# MCPAmplifier.net
KiCad netlist of a schematic drawn in EAGLE
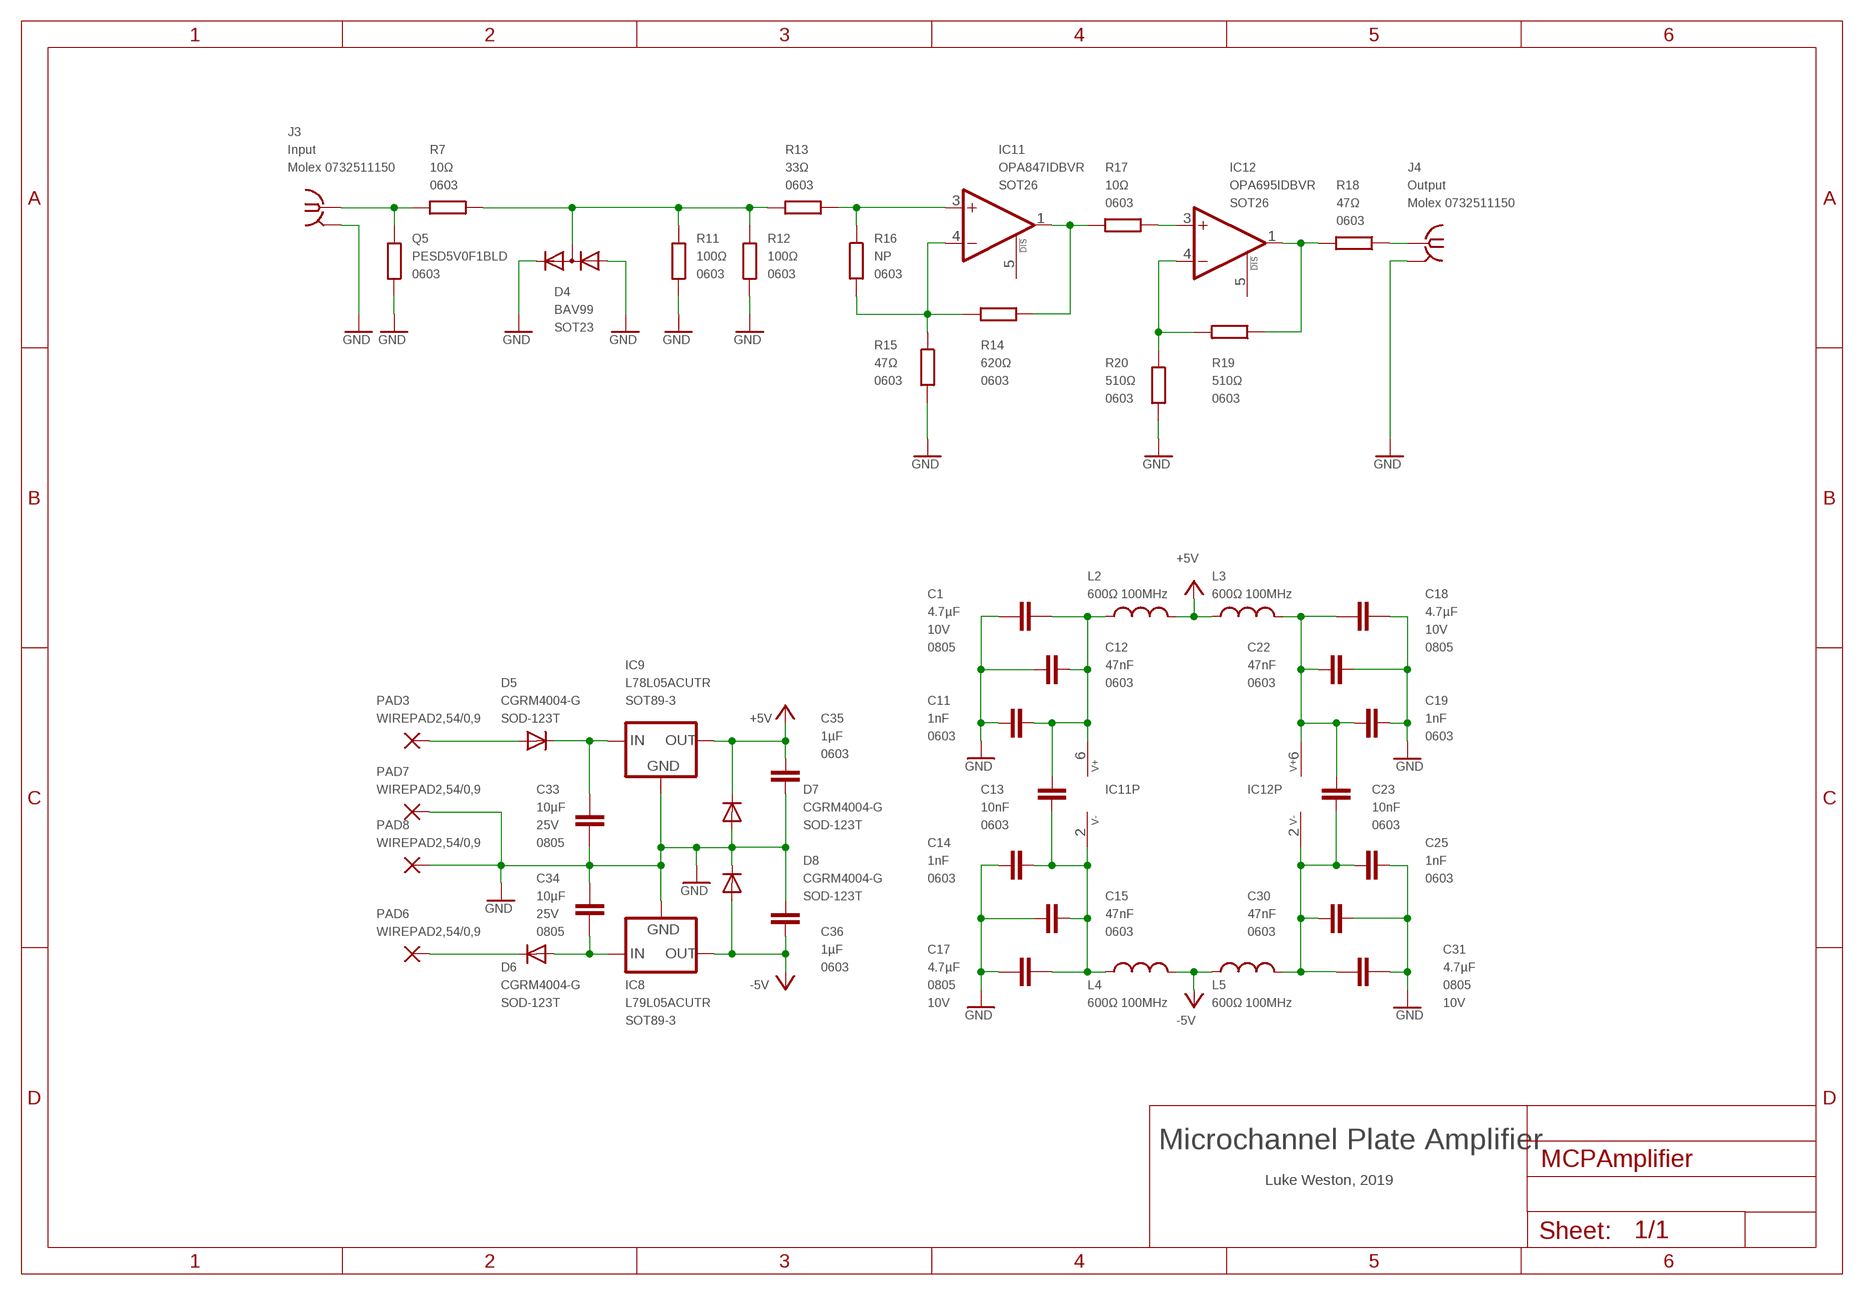
[diagram p0: schematic, sheet 1]

(export (version "E")
  (design (tool "Eeschema 10.0.6"))
  (components
    (comp (ref "C1")
      (value "4.7µF")
      (footprint "eagle-import:0805")
      (fields (field (name "PACKAGE") "0805") (field (name "VOLTAGE") "10V"))
      (libsource (lib "eagle-import") (part "CAP0805"))
    )
    (comp (ref "C11")
      (value "1nF")
      (footprint "eagle-import:0603")
      (fields (field (name "PACKAGE") "0603"))
      (libsource (lib "eagle-import") (part "C0603"))
    )
    (comp (ref "C12")
      (value "47nF")
      (footprint "eagle-import:0603")
      (fields (field (name "PACKAGE") "0603"))
      (libsource (lib "eagle-import") (part "C0603"))
    )
    (comp (ref "C13")
      (value "10nF")
      (footprint "eagle-import:0603")
      (fields (field (name "PACKAGE") "0603"))
      (libsource (lib "eagle-import") (part "C0603"))
    )
    (comp (ref "C14")
      (value "1nF")
      (footprint "eagle-import:0603")
      (fields (field (name "PACKAGE") "0603"))
      (libsource (lib "eagle-import") (part "C0603"))
    )
    (comp (ref "C15")
      (value "47nF")
      (footprint "eagle-import:0603")
      (fields (field (name "PACKAGE") "0603"))
      (libsource (lib "eagle-import") (part "C0603"))
    )
    (comp (ref "C17")
      (value "4.7µF")
      (footprint "eagle-import:0805")
      (fields (field (name "PACKAGE") "0805") (field (name "VOLTAGE") "10V"))
      (libsource (lib "eagle-import") (part "CAP0805"))
    )
    (comp (ref "C18")
      (value "4.7µF")
      (footprint "eagle-import:0805")
      (fields (field (name "PACKAGE") "0805") (field (name "VOLTAGE") "10V"))
      (libsource (lib "eagle-import") (part "CAP0805"))
    )
    (comp (ref "C19")
      (value "1nF")
      (footprint "eagle-import:0603")
      (fields (field (name "PACKAGE") "0603"))
      (libsource (lib "eagle-import") (part "C0603"))
    )
    (comp (ref "C22")
      (value "47nF")
      (footprint "eagle-import:0603")
      (fields (field (name "PACKAGE") "0603"))
      (libsource (lib "eagle-import") (part "C0603"))
    )
    (comp (ref "C23")
      (value "10nF")
      (footprint "eagle-import:0603")
      (fields (field (name "PACKAGE") "0603"))
      (libsource (lib "eagle-import") (part "C0603"))
    )
    (comp (ref "C25")
      (value "1nF")
      (footprint "eagle-import:0603")
      (fields (field (name "PACKAGE") "0603"))
      (libsource (lib "eagle-import") (part "C0603"))
    )
    (comp (ref "C30")
      (value "47nF")
      (footprint "eagle-import:0603")
      (fields (field (name "PACKAGE") "0603"))
      (libsource (lib "eagle-import") (part "C0603"))
    )
    (comp (ref "C31")
      (value "4.7µF")
      (footprint "eagle-import:0805")
      (fields (field (name "PACKAGE") "0805") (field (name "VOLTAGE") "10V"))
      (libsource (lib "eagle-import") (part "CAP0805"))
    )
    (comp (ref "C33")
      (value "10µF")
      (footprint "eagle-import:0805")
      (fields (field (name "PACKAGE") "0805") (field (name "VOLTAGE") "25V"))
      (libsource (lib "eagle-import") (part "CAP0805"))
    )
    (comp (ref "C34")
      (value "10µF")
      (footprint "eagle-import:0805")
      (fields (field (name "PACKAGE") "0805") (field (name "VOLTAGE") "25V"))
      (libsource (lib "eagle-import") (part "CAP0805"))
    )
    (comp (ref "C35")
      (value "1µF")
      (footprint "eagle-import:0603")
      (fields (field (name "PACKAGE") "0603"))
      (libsource (lib "eagle-import") (part "C0603"))
    )
    (comp (ref "C36")
      (value "1µF")
      (footprint "eagle-import:0603")
      (fields (field (name "PACKAGE") "0603"))
      (libsource (lib "eagle-import") (part "C0603"))
    )
    (comp (ref "D4")
      (value "BAV99")
      (footprint "eagle-import:SOT23")
      (fields (field (name "PACKAGE") "SOT23"))
      (libsource (lib "eagle-import") (part "BAV199"))
    )
    (comp (ref "D5")
      (value "CGRM4004-G")
      (footprint "eagle-import:SOD-123_MINI-SMA")
      (fields (field (name "PACKAGE") "SOD-123T"))
      (libsource (lib "eagle-import") (part "CGRM400-G4"))
    )
    (comp (ref "D6")
      (value "CGRM4004-G")
      (footprint "eagle-import:SOD-123_MINI-SMA")
      (fields (field (name "PACKAGE") "SOD-123T"))
      (libsource (lib "eagle-import") (part "CGRM400-G4"))
    )
    (comp (ref "D7")
      (value "CGRM4004-G")
      (footprint "eagle-import:SOD-123_MINI-SMA")
      (fields (field (name "PACKAGE") "SOD-123T"))
      (libsource (lib "eagle-import") (part "CGRM400-G4"))
    )
    (comp (ref "D8")
      (value "CGRM4004-G")
      (footprint "eagle-import:SOD-123_MINI-SMA")
      (fields (field (name "PACKAGE") "SOD-123T"))
      (libsource (lib "eagle-import") (part "CGRM400-G4"))
    )
    (comp (ref "IC8")
      (value "L79L05ACUTR")
      (footprint "eagle-import:SOT89")
      (fields (field (name "PACKAGE") "SOT89-3"))
      (libsource (lib "eagle-import") (part "79LXX-SOT89"))
    )
    (comp (ref "IC9")
      (value "L78L05ACUTR")
      (footprint "eagle-import:SOT89")
      (fields (field (name "PACKAGE") "SOT89-3"))
      (libsource (lib "eagle-import") (part "78LXX-SOT89"))
    )
    (comp (ref "IC11")
      (value "OPA847IDBVR")
      (footprint "eagle-import:SOT23-6")
      (fields (field (name "PACKAGE") "SOT26"))
      (libsource (lib "eagle-import") (part "OPA847DBV"))
    )
    (comp (ref "IC12")
      (value "OPA695IDBVR")
      (footprint "eagle-import:SOT23-6")
      (fields (field (name "PACKAGE") "SOT26"))
      (libsource (lib "eagle-import") (part "OPA847DBV"))
    )
    (comp (ref "J3")
      (value "Input")
      (footprint "eagle-import:J502-ND-142-0701-881_886")
      (fields
        (field (name "MF") "JOHNSON COMPONENTS")
        (field (name "MPN") "142-0701-881")
        (field (name "SKU") "Molex 0732511150")
      )
      (libsource (lib "eagle-import") (part "SMA-142-0701-881/886"))
    )
    (comp (ref "J4")
      (value "Output")
      (footprint "eagle-import:J502-ND-142-0701-881_886")
      (fields
        (field (name "MF") "JOHNSON COMPONENTS")
        (field (name "MPN") "142-0701-881")
        (field (name "SKU") "Molex 0732511150")
      )
      (libsource (lib "eagle-import") (part "SMA-142-0701-881/886"))
    )
    (comp (ref "L2")
      (value "600Ω 100MHz")
      (footprint "eagle-import:0603")
      (libsource (lib "eagle-import") (part "0402INDUCTOR"))
    )
    (comp (ref "L3")
      (value "600Ω 100MHz")
      (footprint "eagle-import:0603")
      (libsource (lib "eagle-import") (part "0402INDUCTOR"))
    )
    (comp (ref "L4")
      (value "600Ω 100MHz")
      (footprint "eagle-import:0603")
      (libsource (lib "eagle-import") (part "0402INDUCTOR"))
    )
    (comp (ref "L5")
      (value "600Ω 100MHz")
      (footprint "eagle-import:0603")
      (libsource (lib "eagle-import") (part "0402INDUCTOR"))
    )
    (comp (ref "PAD3")
      (value "WIREPAD2,54/0,9")
      (footprint "eagle-import:2,54_0,9")
      (libsource (lib "eagle-import") (part "WIREPAD2,54/0,9"))
    )
    (comp (ref "PAD6")
      (value "WIREPAD2,54/0,9")
      (footprint "eagle-import:2,54_0,9")
      (libsource (lib "eagle-import") (part "WIREPAD2,54/0,9"))
    )
    (comp (ref "PAD7")
      (value "WIREPAD2,54/0,9")
      (footprint "eagle-import:2,54_0,9")
      (libsource (lib "eagle-import") (part "WIREPAD2,54/0,9"))
    )
    (comp (ref "PAD8")
      (value "WIREPAD2,54/0,9")
      (footprint "eagle-import:2,54_0,9")
      (libsource (lib "eagle-import") (part "WIREPAD2,54/0,9"))
    )
    (comp (ref "Q5")
      (value "PESD5V0F1BLD")
      (footprint "eagle-import:0603")
      (fields (field (name "PACKAGE") "0603"))
      (libsource (lib "eagle-import") (part "R0603"))
    )
    (comp (ref "R7")
      (value "10Ω")
      (footprint "eagle-import:0603")
      (fields (field (name "PACKAGE") "0603"))
      (libsource (lib "eagle-import") (part "R0603"))
    )
    (comp (ref "R11")
      (value "100Ω")
      (footprint "eagle-import:0603")
      (fields (field (name "PACKAGE") "0603"))
      (libsource (lib "eagle-import") (part "R0603"))
    )
    (comp (ref "R12")
      (value "100Ω")
      (footprint "eagle-import:0603")
      (fields (field (name "PACKAGE") "0603"))
      (libsource (lib "eagle-import") (part "R0603"))
    )
    (comp (ref "R13")
      (value "33Ω")
      (footprint "eagle-import:0603")
      (fields (field (name "PACKAGE") "0603"))
      (libsource (lib "eagle-import") (part "R0603"))
    )
    (comp (ref "R14")
      (value "620Ω")
      (footprint "eagle-import:0603")
      (fields (field (name "PACKAGE") "0603"))
      (libsource (lib "eagle-import") (part "R0603"))
    )
    (comp (ref "R15")
      (value "47Ω")
      (footprint "eagle-import:0603")
      (fields (field (name "PACKAGE") "0603"))
      (libsource (lib "eagle-import") (part "R0603"))
    )
    (comp (ref "R16")
      (value "NP")
      (footprint "eagle-import:0603")
      (fields (field (name "PACKAGE") "0603"))
      (libsource (lib "eagle-import") (part "R0603"))
    )
    (comp (ref "R17")
      (value "10Ω")
      (footprint "eagle-import:0603")
      (fields (field (name "PACKAGE") "0603"))
      (libsource (lib "eagle-import") (part "R0603"))
    )
    (comp (ref "R18")
      (value "47Ω")
      (footprint "eagle-import:0603")
      (fields (field (name "PACKAGE") "0603"))
      (libsource (lib "eagle-import") (part "R0603"))
    )
    (comp (ref "R19")
      (value "510Ω")
      (footprint "eagle-import:0603")
      (fields (field (name "PACKAGE") "0603"))
      (libsource (lib "eagle-import") (part "R0603"))
    )
    (comp (ref "R20")
      (value "510Ω")
      (footprint "eagle-import:0603")
      (fields (field (name "PACKAGE") "0603"))
      (libsource (lib "eagle-import") (part "R0603"))
    )
  )
  (nets
    (net (code "1") (name "+5V") (class "Default")
      (node (ref "C35") (pin "1") (pinfunction "1_1") (pintype "passive"))
      (node (ref "D7") (pin "C") (pinfunction "C_C") (pintype "passive"))
      (node (ref "IC9") (pin "1") (pinfunction "OUT_1") (pintype "passive"))
      (node (ref "L2") (pin "2") (pinfunction "2_2") (pintype "bidirectional"))
      (node (ref "L3") (pin "1") (pinfunction "1_1") (pintype "bidirectional"))
    )
    (net (code "2") (name "-5V") (class "Default")
      (node (ref "C36") (pin "2") (pinfunction "2_2") (pintype "passive"))
      (node (ref "D8") (pin "A") (pinfunction "A_A") (pintype "passive"))
      (node (ref "IC8") (pin "3") (pinfunction "OUT_3") (pintype "passive"))
      (node (ref "L4") (pin "2") (pinfunction "2_2") (pintype "bidirectional"))
      (node (ref "L5") (pin "1") (pinfunction "1_1") (pintype "bidirectional"))
    )
    (net (code "3") (name "/GND") (class "Default")
      (node (ref "C1") (pin "2") (pinfunction "2_2") (pintype "passive"))
      (node (ref "C11") (pin "2") (pinfunction "2_2") (pintype "passive"))
      (node (ref "C12") (pin "2") (pinfunction "2_2") (pintype "passive"))
      (node (ref "C14") (pin "2") (pinfunction "2_2") (pintype "passive"))
      (node (ref "C15") (pin "2") (pinfunction "2_2") (pintype "passive"))
      (node (ref "C17") (pin "2") (pinfunction "2_2") (pintype "passive"))
      (node (ref "C18") (pin "2") (pinfunction "2_2") (pintype "passive"))
      (node (ref "C19") (pin "2") (pinfunction "2_2") (pintype "passive"))
      (node (ref "C22") (pin "2") (pinfunction "2_2") (pintype "passive"))
      (node (ref "C25") (pin "2") (pinfunction "2_2") (pintype "passive"))
      (node (ref "C30") (pin "2") (pinfunction "2_2") (pintype "passive"))
      (node (ref "C31") (pin "2") (pinfunction "2_2") (pintype "passive"))
      (node (ref "C33") (pin "1") (pinfunction "1_1") (pintype "passive"))
      (node (ref "C34") (pin "2") (pinfunction "2_2") (pintype "passive"))
      (node (ref "C35") (pin "2") (pinfunction "2_2") (pintype "passive"))
      (node (ref "C36") (pin "1") (pinfunction "1_1") (pintype "passive"))
      (node (ref "D4") (pin "1") (pinfunction "A_1") (pintype "passive"))
      (node (ref "D4") (pin "2") (pinfunction "C_2") (pintype "passive"))
      (node (ref "D7") (pin "A") (pinfunction "A_A") (pintype "passive"))
      (node (ref "D8") (pin "C") (pinfunction "C_C") (pintype "passive"))
      (node (ref "IC8") (pin "1") (pinfunction "GND_1") (pintype "input"))
      (node (ref "IC9") (pin "2") (pinfunction "GND_2") (pintype "input"))
      (node (ref "J3") (pin "G@1") (pinfunction "2_G@1") (pintype "passive"))
      (node (ref "J3") (pin "G@2") (pinfunction "2_G@2") (pintype "passive"))
      (node (ref "J3") (pin "G@3") (pinfunction "2_G@3") (pintype "passive"))
      (node (ref "J3") (pin "G@4") (pinfunction "2_G@4") (pintype "passive"))
      (node (ref "J4") (pin "G@1") (pinfunction "2_G@1") (pintype "passive"))
      (node (ref "J4") (pin "G@2") (pinfunction "2_G@2") (pintype "passive"))
      (node (ref "J4") (pin "G@3") (pinfunction "2_G@3") (pintype "passive"))
      (node (ref "J4") (pin "G@4") (pinfunction "2_G@4") (pintype "passive"))
      (node (ref "PAD7") (pin "1") (pinfunction "P_1") (pintype "passive"))
      (node (ref "PAD8") (pin "1") (pinfunction "P_1") (pintype "passive"))
      (node (ref "Q5") (pin "1") (pinfunction "1_1") (pintype "passive"))
      (node (ref "R11") (pin "1") (pinfunction "1_1") (pintype "passive"))
      (node (ref "R12") (pin "1") (pinfunction "1_1") (pintype "passive"))
      (node (ref "R15") (pin "2") (pinfunction "2_2") (pintype "passive"))
      (node (ref "R20") (pin "2") (pinfunction "2_2") (pintype "passive"))
    )
    (net (code "4") (name "Net-(D4-AC)") (class "Default")
      (node (ref "D4") (pin "3") (pinfunction "AC_3") (pintype "passive"))
      (node (ref "R11") (pin "2") (pinfunction "2_2") (pintype "passive"))
      (node (ref "R12") (pin "2") (pinfunction "2_2") (pintype "passive"))
      (node (ref "R13") (pin "2") (pinfunction "2_2") (pintype "passive"))
      (node (ref "R7") (pin "2") (pinfunction "2_2") (pintype "passive"))
    )
    (net (code "5") (name "Net-(IC8-IN)") (class "Default")
      (node (ref "C34") (pin "1") (pinfunction "1_1") (pintype "passive"))
      (node (ref "D6") (pin "A") (pinfunction "A_A") (pintype "passive"))
      (node (ref "IC8") (pin "2") (pinfunction "IN_2") (pintype "input"))
    )
    (net (code "6") (name "Net-(IC9-IN)") (class "Default")
      (node (ref "C33") (pin "2") (pinfunction "2_2") (pintype "passive"))
      (node (ref "D5") (pin "C") (pinfunction "C_C") (pintype "passive"))
      (node (ref "IC9") (pin "3") (pinfunction "IN_3") (pintype "input"))
    )
    (net (code "7") (name "Net-(IC11A-+IN)") (class "Default")
      (node (ref "IC11") (pin "3") (pinfunction "+IN_3") (pintype "input"))
      (node (ref "R13") (pin "1") (pinfunction "1_1") (pintype "passive"))
      (node (ref "R16") (pin "1") (pinfunction "1_1") (pintype "passive"))
    )
    (net (code "8") (name "Net-(IC11A--IN)") (class "Default")
      (node (ref "IC11") (pin "4") (pinfunction "-IN_4") (pintype "input"))
      (node (ref "R14") (pin "2") (pinfunction "2_2") (pintype "passive"))
      (node (ref "R15") (pin "1") (pinfunction "1_1") (pintype "passive"))
      (node (ref "R16") (pin "2") (pinfunction "2_2") (pintype "passive"))
    )
    (net (code "9") (name "Net-(IC11A-OUT)") (class "Default")
      (node (ref "IC11") (pin "1") (pinfunction "OUT_1") (pintype "output"))
      (node (ref "R14") (pin "1") (pinfunction "1_1") (pintype "passive"))
      (node (ref "R17") (pin "2") (pinfunction "2_2") (pintype "passive"))
    )
    (net (code "10") (name "Net-(IC11B-V+)") (class "Default")
      (node (ref "C1") (pin "1") (pinfunction "1_1") (pintype "passive"))
      (node (ref "C11") (pin "1") (pinfunction "1_1") (pintype "passive"))
      (node (ref "C12") (pin "1") (pinfunction "1_1") (pintype "passive"))
      (node (ref "C13") (pin "1") (pinfunction "1_1") (pintype "passive"))
      (node (ref "IC11") (pin "6") (pinfunction "V+_6") (pintype "power_in"))
      (node (ref "L2") (pin "1") (pinfunction "1_1") (pintype "bidirectional"))
    )
    (net (code "11") (name "Net-(IC11B-V-)") (class "Default")
      (node (ref "C13") (pin "2") (pinfunction "2_2") (pintype "passive"))
      (node (ref "C14") (pin "1") (pinfunction "1_1") (pintype "passive"))
      (node (ref "C15") (pin "1") (pinfunction "1_1") (pintype "passive"))
      (node (ref "C17") (pin "1") (pinfunction "1_1") (pintype "passive"))
      (node (ref "IC11") (pin "2") (pinfunction "V-_2") (pintype "power_in"))
      (node (ref "L4") (pin "1") (pinfunction "1_1") (pintype "bidirectional"))
    )
    (net (code "12") (name "Net-(IC12A-+IN)") (class "Default")
      (node (ref "IC12") (pin "3") (pinfunction "+IN_3") (pintype "input"))
      (node (ref "R17") (pin "1") (pinfunction "1_1") (pintype "passive"))
    )
    (net (code "13") (name "Net-(IC12A--IN)") (class "Default")
      (node (ref "IC12") (pin "4") (pinfunction "-IN_4") (pintype "input"))
      (node (ref "R19") (pin "2") (pinfunction "2_2") (pintype "passive"))
      (node (ref "R20") (pin "1") (pinfunction "1_1") (pintype "passive"))
    )
    (net (code "14") (name "Net-(IC12A-OUT)") (class "Default")
      (node (ref "IC12") (pin "1") (pinfunction "OUT_1") (pintype "output"))
      (node (ref "R18") (pin "2") (pinfunction "2_2") (pintype "passive"))
      (node (ref "R19") (pin "1") (pinfunction "1_1") (pintype "passive"))
    )
    (net (code "15") (name "Net-(IC12B-V+)") (class "Default")
      (node (ref "C18") (pin "1") (pinfunction "1_1") (pintype "passive"))
      (node (ref "C19") (pin "1") (pinfunction "1_1") (pintype "passive"))
      (node (ref "C22") (pin "1") (pinfunction "1_1") (pintype "passive"))
      (node (ref "C23") (pin "1") (pinfunction "1_1") (pintype "passive"))
      (node (ref "IC12") (pin "6") (pinfunction "V+_6") (pintype "power_in"))
      (node (ref "L3") (pin "2") (pinfunction "2_2") (pintype "bidirectional"))
    )
    (net (code "16") (name "Net-(IC12B-V-)") (class "Default")
      (node (ref "C23") (pin "2") (pinfunction "2_2") (pintype "passive"))
      (node (ref "C25") (pin "1") (pinfunction "1_1") (pintype "passive"))
      (node (ref "C30") (pin "1") (pinfunction "1_1") (pintype "passive"))
      (node (ref "C31") (pin "1") (pinfunction "1_1") (pintype "passive"))
      (node (ref "IC12") (pin "2") (pinfunction "V-_2") (pintype "power_in"))
      (node (ref "L5") (pin "2") (pinfunction "2_2") (pintype "bidirectional"))
    )
    (net (code "17") (name "Net-(J3-Pad1)") (class "Default")
      (node (ref "J3") (pin "1") (pinfunction "1_1") (pintype "passive"))
      (node (ref "Q5") (pin "2") (pinfunction "2_2") (pintype "passive"))
      (node (ref "R7") (pin "1") (pinfunction "1_1") (pintype "passive"))
    )
    (net (code "18") (name "Net-(J4-Pad1)") (class "Default")
      (node (ref "J4") (pin "1") (pinfunction "1_1") (pintype "passive"))
      (node (ref "R18") (pin "1") (pinfunction "1_1") (pintype "passive"))
    )
    (net (code "19") (name "Net-(PAD3-P)") (class "Default")
      (node (ref "D5") (pin "A") (pinfunction "A_A") (pintype "passive"))
      (node (ref "PAD3") (pin "1") (pinfunction "P_1") (pintype "passive"))
    )
    (net (code "20") (name "Net-(PAD6-P)") (class "Default")
      (node (ref "D6") (pin "C") (pinfunction "C_C") (pintype "passive"))
      (node (ref "PAD6") (pin "1") (pinfunction "P_1") (pintype "passive"))
    )
    (net (code "21") (name "unconnected-(IC11A-DIS-Pad5)") (class "Default")
      (node (ref "IC11") (pin "5") (pinfunction "DIS_5") (pintype "passive"))
    )
    (net (code "22") (name "unconnected-(IC12A-DIS-Pad5)") (class "Default")
      (node (ref "IC12") (pin "5") (pinfunction "DIS_5") (pintype "passive"))
    )
  )
)
